# IOExpand.net
KiCad netlist of a schematic drawn in Altium Designer
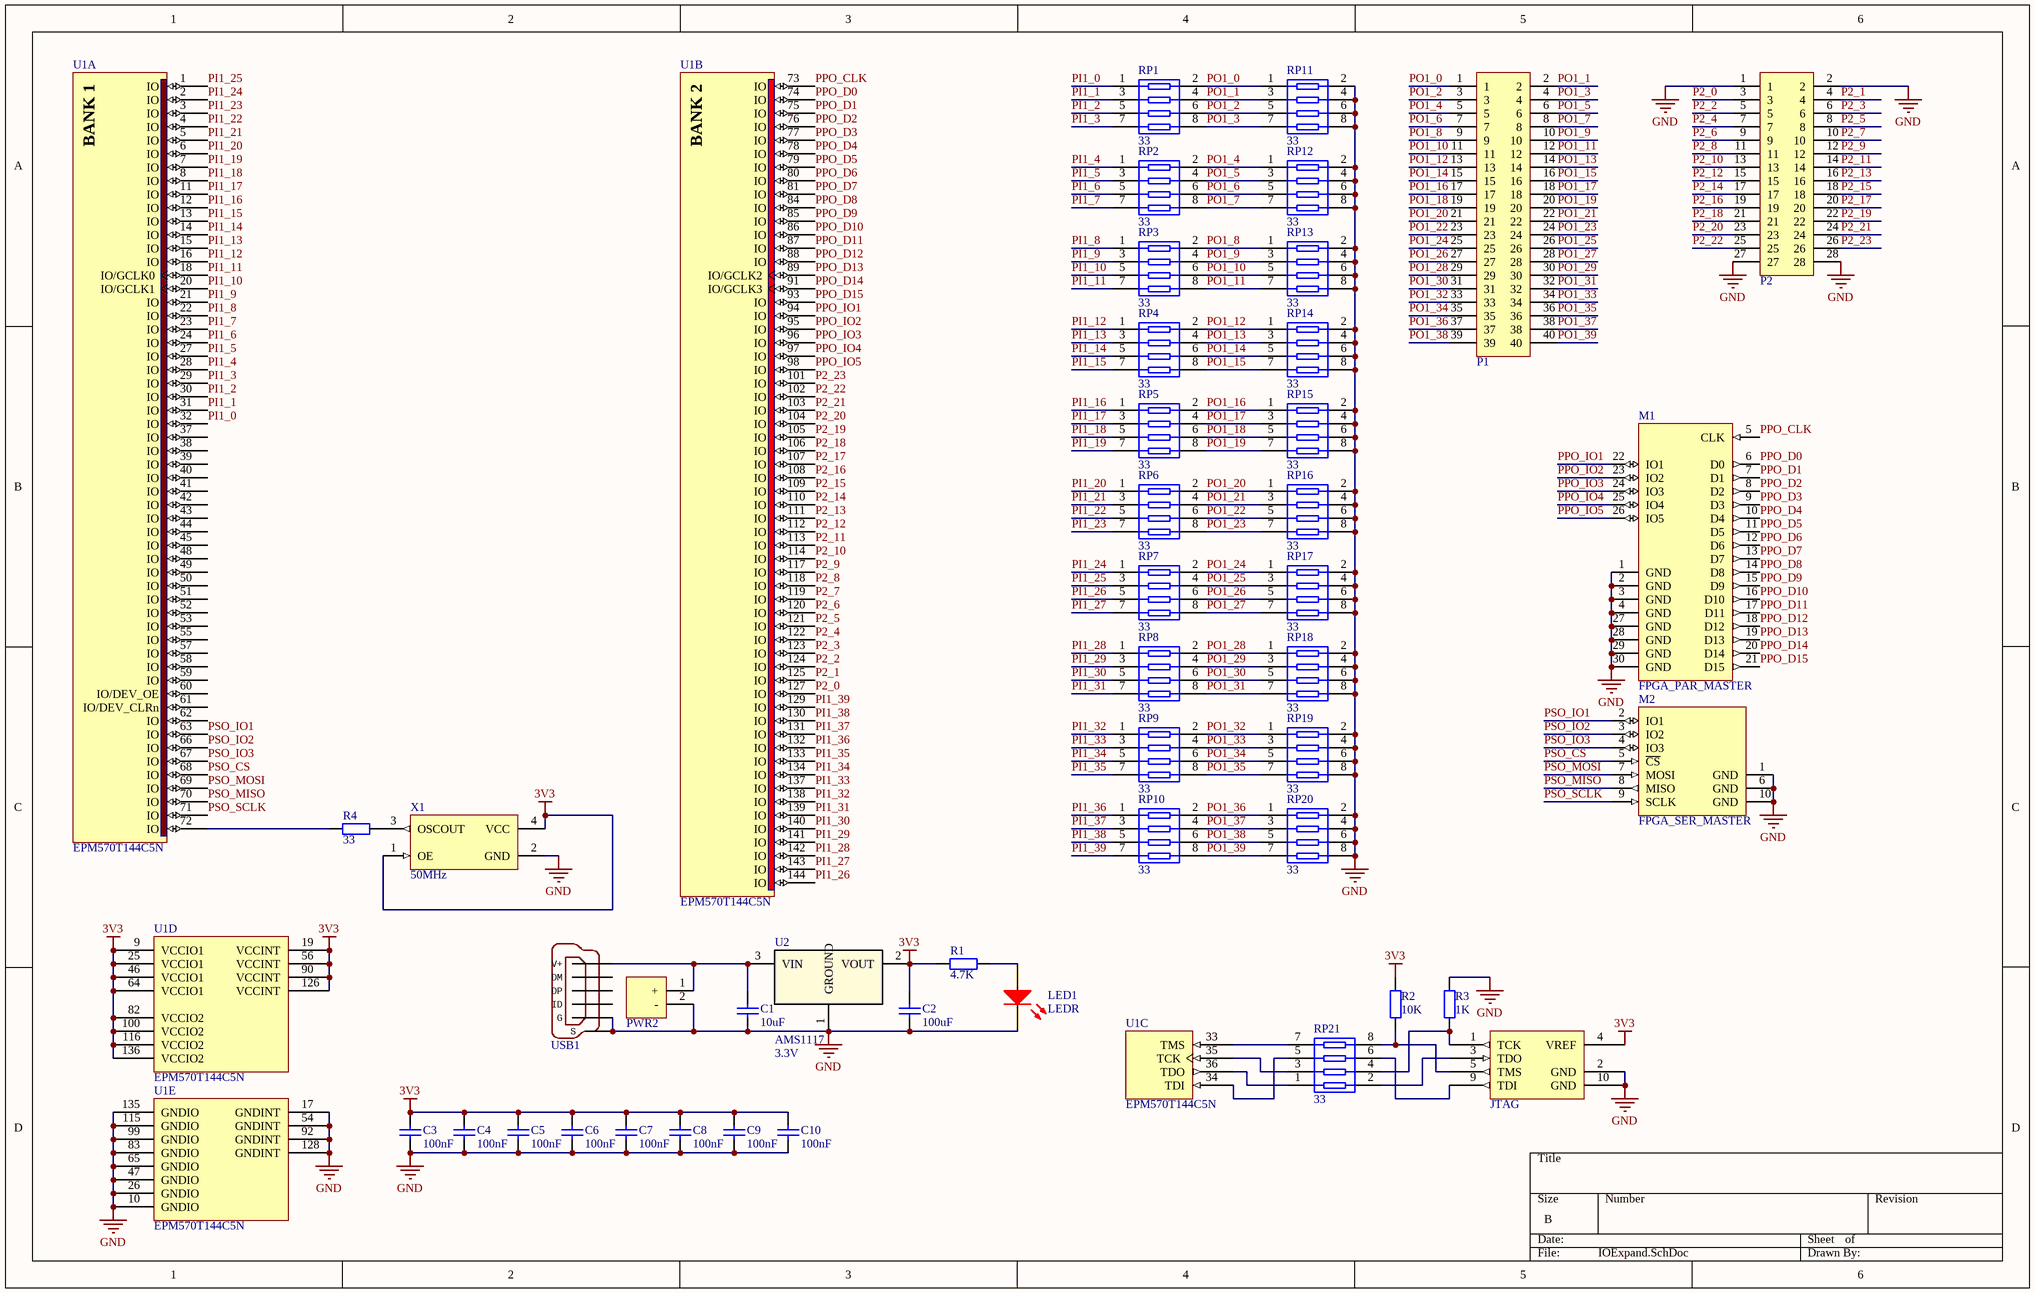
[diagram p0: IOExpand.SchDoc]

(export (version "E")
  (design (tool "Eeschema 10.0.6"))
  (components
    (comp (ref "C1")
      (value "10uF")
      (footprint "0805C")
      (description "MLCC")
      (libsource (lib "Misc") (part "MLCC"))
    )
    (comp (ref "C2")
      (value "100uF")
      (footprint "1206C")
      (description "MLCC")
      (libsource (lib "Misc") (part "MLCC"))
    )
    (comp (ref "C3")
      (value "100nF")
      (footprint "0603C")
      (description "MLCC")
      (libsource (lib "Misc") (part "MLCC"))
    )
    (comp (ref "C4")
      (value "100nF")
      (footprint "0603C")
      (description "MLCC")
      (libsource (lib "Misc") (part "MLCC"))
    )
    (comp (ref "C5")
      (value "100nF")
      (footprint "0603C")
      (description "MLCC")
      (libsource (lib "Misc") (part "MLCC"))
    )
    (comp (ref "C6")
      (value "100nF")
      (footprint "0603C")
      (description "MLCC")
      (libsource (lib "Misc") (part "MLCC"))
    )
    (comp (ref "C7")
      (value "100nF")
      (footprint "0603C")
      (description "MLCC")
      (libsource (lib "Misc") (part "MLCC"))
    )
    (comp (ref "C8")
      (value "100nF")
      (footprint "0603C")
      (description "MLCC")
      (libsource (lib "Misc") (part "MLCC"))
    )
    (comp (ref "C9")
      (value "100nF")
      (footprint "0603C")
      (description "MLCC")
      (libsource (lib "Misc") (part "MLCC"))
    )
    (comp (ref "C10")
      (value "100nF")
      (footprint "0603C")
      (description "MLCC")
      (libsource (lib "Misc") (part "MLCC"))
    )
    (comp (ref "JTAG")
      (value "JTAG_ALTERA")
      (footprint "JTAG10")
      (description "ALTERA JTAG port")
      (libsource (lib "JTAG") (part "JTAG_ALTERA"))
    )
    (comp (ref "LED1")
      (value "LEDR")
      (footprint "LED1206R")
      (description "RED LED")
      (libsource (lib "Misc") (part "LEDR"))
    )
    (comp (ref "M1")
      (value "FPGA_PAR_MASTER")
      (footprint "IDC30")
      (description "FPGA parallel port")
      (libsource (lib "Modules") (part "FPGA_PAR_MASTER"))
    )
    (comp (ref "M2")
      (value "FPGA_SER_MASTER")
      (footprint "IDC10")
      (description "FPGA serial port")
      (libsource (lib "Modules") (part "FPGA_SER_MASTER"))
    )
    (comp (ref "P1")
      (value "Dual 20 pin port")
      (footprint "201S2X20")
      (libsource (lib "Ports2.54") (part "DPORT20"))
    )
    (comp (ref "P2")
      (value "Dual 14 pin port")
      (footprint "201S2X14")
      (libsource (lib "Ports2.54") (part "DPORT14"))
    )
    (comp (ref "PWR2")
      (value "WPORT2_PWR")
      (footprint "VH3.96-POWER-2P")
      (description "2 pin power port")
      (libsource (lib "Ports3.96") (part "WPORT2_PWR"))
    )
    (comp (ref "R1")
      (value "4.7K")
      (footprint "0603R")
      (description "Resistor")
      (libsource (lib "Misc") (part "Resistor"))
    )
    (comp (ref "R2")
      (value "10K")
      (footprint "0603R")
      (description "Resistor")
      (libsource (lib "") (part "Resistor_1"))
    )
    (comp (ref "R3")
      (value "1K")
      (footprint "0603R")
      (description "Resistor")
      (libsource (lib "") (part "Resistor_1"))
    )
    (comp (ref "R4")
      (value "33")
      (footprint "0603R")
      (description "Resistor")
      (libsource (lib "Misc") (part "Resistor"))
    )
    (comp (ref "RP1")
      (value "33")
      (footprint "8P4R_0603")
      (description "Isolated Resistor Network")
      (fields (field (name "Comment") "Res Pack"))
      (libsource (lib "Misc") (part "Res Pack"))
    )
    (comp (ref "RP2")
      (value "33")
      (footprint "8P4R_0603")
      (description "Isolated Resistor Network")
      (fields (field (name "Comment") "Res Pack"))
      (libsource (lib "Misc") (part "Res Pack"))
    )
    (comp (ref "RP3")
      (value "33")
      (footprint "8P4R_0603")
      (description "Isolated Resistor Network")
      (fields (field (name "Comment") "Res Pack"))
      (libsource (lib "Misc") (part "Res Pack"))
    )
    (comp (ref "RP4")
      (value "33")
      (footprint "8P4R_0603")
      (description "Isolated Resistor Network")
      (fields (field (name "Comment") "Res Pack"))
      (libsource (lib "Misc") (part "Res Pack"))
    )
    (comp (ref "RP5")
      (value "33")
      (footprint "8P4R_0603")
      (description "Isolated Resistor Network")
      (fields (field (name "Comment") "Res Pack"))
      (libsource (lib "Misc") (part "Res Pack"))
    )
    (comp (ref "RP6")
      (value "33")
      (footprint "8P4R_0603")
      (description "Isolated Resistor Network")
      (fields (field (name "Comment") "Res Pack"))
      (libsource (lib "Misc") (part "Res Pack"))
    )
    (comp (ref "RP7")
      (value "33")
      (footprint "8P4R_0603")
      (description "Isolated Resistor Network")
      (fields (field (name "Comment") "Res Pack"))
      (libsource (lib "Misc") (part "Res Pack"))
    )
    (comp (ref "RP8")
      (value "33")
      (footprint "8P4R_0603")
      (description "Isolated Resistor Network")
      (fields (field (name "Comment") "Res Pack"))
      (libsource (lib "Misc") (part "Res Pack"))
    )
    (comp (ref "RP9")
      (value "33")
      (footprint "8P4R_0603")
      (description "Isolated Resistor Network")
      (fields (field (name "Comment") "Res Pack"))
      (libsource (lib "Misc") (part "Res Pack"))
    )
    (comp (ref "RP10")
      (value "33")
      (footprint "8P4R_0603")
      (description "Isolated Resistor Network")
      (fields (field (name "Comment") "Res Pack"))
      (libsource (lib "Misc") (part "Res Pack"))
    )
    (comp (ref "RP11")
      (value "33")
      (footprint "8P4R_0603")
      (description "Isolated Resistor Network")
      (fields (field (name "Comment") "Res Pack"))
      (libsource (lib "Misc") (part "Res Pack"))
    )
    (comp (ref "RP12")
      (value "33")
      (footprint "8P4R_0603")
      (description "Isolated Resistor Network")
      (fields (field (name "Comment") "Res Pack"))
      (libsource (lib "Misc") (part "Res Pack"))
    )
    (comp (ref "RP13")
      (value "33")
      (footprint "8P4R_0603")
      (description "Isolated Resistor Network")
      (fields (field (name "Comment") "Res Pack"))
      (libsource (lib "Misc") (part "Res Pack"))
    )
    (comp (ref "RP14")
      (value "33")
      (footprint "8P4R_0603")
      (description "Isolated Resistor Network")
      (fields (field (name "Comment") "Res Pack"))
      (libsource (lib "Misc") (part "Res Pack"))
    )
    (comp (ref "RP15")
      (value "33")
      (footprint "8P4R_0603")
      (description "Isolated Resistor Network")
      (fields (field (name "Comment") "Res Pack"))
      (libsource (lib "Misc") (part "Res Pack"))
    )
    (comp (ref "RP16")
      (value "33")
      (footprint "8P4R_0603")
      (description "Isolated Resistor Network")
      (fields (field (name "Comment") "Res Pack"))
      (libsource (lib "Misc") (part "Res Pack"))
    )
    (comp (ref "RP17")
      (value "33")
      (footprint "8P4R_0603")
      (description "Isolated Resistor Network")
      (fields (field (name "Comment") "Res Pack"))
      (libsource (lib "Misc") (part "Res Pack"))
    )
    (comp (ref "RP18")
      (value "33")
      (footprint "8P4R_0603")
      (description "Isolated Resistor Network")
      (fields (field (name "Comment") "Res Pack"))
      (libsource (lib "Misc") (part "Res Pack"))
    )
    (comp (ref "RP19")
      (value "33")
      (footprint "8P4R_0603")
      (description "Isolated Resistor Network")
      (fields (field (name "Comment") "Res Pack"))
      (libsource (lib "Misc") (part "Res Pack"))
    )
    (comp (ref "RP20")
      (value "33")
      (footprint "8P4R_0603")
      (description "Isolated Resistor Network")
      (fields (field (name "Comment") "Res Pack"))
      (libsource (lib "Misc") (part "Res Pack"))
    )
    (comp (ref "RP21")
      (value "33")
      (footprint "8P4R_0603")
      (description "Isolated Resistor Network")
      (fields (field (name "Comment") "Res Pack"))
      (libsource (lib "Misc") (part "Res Pack"))
    )
    (comp (ref "U1")
      (value "EPM570T144C5N")
      (footprint "TQFP144_N")
      (libsource (lib "Altera MAX II") (part "EPM570T144C5N"))
    )
    (comp (ref "U2")
      (value "AMS1117")
      (footprint "DCY4")
      (description "800mA LOW DROPOUT VOLTAGE REGULATOR")
      (fields (field (name "ALTIUM_VALUE") "3.3V"))
      (libsource (lib "LDO") (part "AMS1117"))
    )
    (comp (ref "USB1")
      (value "MICRO-USB")
      (footprint "USB-MICRO")
      (description "MICRO USB Connector")
      (libsource (lib "Misc") (part "MICRO-USB"))
    )
    (comp (ref "X1")
      (value "50MHz")
      (footprint "XTAL-3225")
      (description "Oscillator")
      (libsource (lib "XTAL") (part "Oscillator"))
    )
  )
  (nets
    (net (code "1") (name "/P2_0") (class "Default")
      (node (ref "P2") (pin "3") (pinfunction "3_3") (pintype "passive"))
      (node (ref "U1") (pin "127") (pinfunction "IO_127") (pintype "bidirectional"))
    )
    (net (code "2") (name "/P2_1") (class "Default")
      (node (ref "P2") (pin "4") (pinfunction "4_4") (pintype "passive"))
      (node (ref "U1") (pin "125") (pinfunction "IO_125") (pintype "bidirectional"))
    )
    (net (code "3") (name "/P2_2") (class "Default")
      (node (ref "P2") (pin "5") (pinfunction "5_5") (pintype "passive"))
      (node (ref "U1") (pin "124") (pinfunction "IO_124") (pintype "bidirectional"))
    )
    (net (code "4") (name "/P2_3") (class "Default")
      (node (ref "P2") (pin "6") (pinfunction "6_6") (pintype "passive"))
      (node (ref "U1") (pin "123") (pinfunction "IO_123") (pintype "bidirectional"))
    )
    (net (code "5") (name "/P2_4") (class "Default")
      (node (ref "P2") (pin "7") (pinfunction "7_7") (pintype "passive"))
      (node (ref "U1") (pin "122") (pinfunction "IO_122") (pintype "bidirectional"))
    )
    (net (code "6") (name "/P2_5") (class "Default")
      (node (ref "P2") (pin "8") (pinfunction "8_8") (pintype "passive"))
      (node (ref "U1") (pin "121") (pinfunction "IO_121") (pintype "bidirectional"))
    )
    (net (code "7") (name "/P2_6") (class "Default")
      (node (ref "P2") (pin "9") (pinfunction "9_9") (pintype "passive"))
      (node (ref "U1") (pin "120") (pinfunction "IO_120") (pintype "bidirectional"))
    )
    (net (code "8") (name "/P2_7") (class "Default")
      (node (ref "P2") (pin "10") (pinfunction "10_10") (pintype "passive"))
      (node (ref "U1") (pin "119") (pinfunction "IO_119") (pintype "bidirectional"))
    )
    (net (code "9") (name "/P2_8") (class "Default")
      (node (ref "P2") (pin "11") (pinfunction "11_11") (pintype "passive"))
      (node (ref "U1") (pin "118") (pinfunction "IO_118") (pintype "bidirectional"))
    )
    (net (code "10") (name "/P2_9") (class "Default")
      (node (ref "P2") (pin "12") (pinfunction "12_12") (pintype "passive"))
      (node (ref "U1") (pin "117") (pinfunction "IO_117") (pintype "bidirectional"))
    )
    (net (code "11") (name "/P2_10") (class "Default")
      (node (ref "P2") (pin "13") (pinfunction "13_13") (pintype "passive"))
      (node (ref "U1") (pin "114") (pinfunction "IO_114") (pintype "bidirectional"))
    )
    (net (code "12") (name "/P2_11") (class "Default")
      (node (ref "P2") (pin "14") (pinfunction "14_14") (pintype "passive"))
      (node (ref "U1") (pin "113") (pinfunction "IO_113") (pintype "bidirectional"))
    )
    (net (code "13") (name "/P2_12") (class "Default")
      (node (ref "P2") (pin "15") (pinfunction "15_15") (pintype "passive"))
      (node (ref "U1") (pin "112") (pinfunction "IO_112") (pintype "bidirectional"))
    )
    (net (code "14") (name "/P2_13") (class "Default")
      (node (ref "P2") (pin "16") (pinfunction "16_16") (pintype "passive"))
      (node (ref "U1") (pin "111") (pinfunction "IO_111") (pintype "bidirectional"))
    )
    (net (code "15") (name "/P2_14") (class "Default")
      (node (ref "P2") (pin "17") (pinfunction "17_17") (pintype "passive"))
      (node (ref "U1") (pin "110") (pinfunction "IO_110") (pintype "bidirectional"))
    )
    (net (code "16") (name "/P2_15") (class "Default")
      (node (ref "P2") (pin "18") (pinfunction "18_18") (pintype "passive"))
      (node (ref "U1") (pin "109") (pinfunction "IO_109") (pintype "bidirectional"))
    )
    (net (code "17") (name "/P2_16") (class "Default")
      (node (ref "P2") (pin "19") (pinfunction "19_19") (pintype "passive"))
      (node (ref "U1") (pin "108") (pinfunction "IO_108") (pintype "bidirectional"))
    )
    (net (code "18") (name "/P2_17") (class "Default")
      (node (ref "P2") (pin "20") (pinfunction "20_20") (pintype "passive"))
      (node (ref "U1") (pin "107") (pinfunction "IO_107") (pintype "bidirectional"))
    )
    (net (code "19") (name "/P2_18") (class "Default")
      (node (ref "P2") (pin "21") (pinfunction "21_21") (pintype "passive"))
      (node (ref "U1") (pin "106") (pinfunction "IO_106") (pintype "bidirectional"))
    )
    (net (code "20") (name "/P2_19") (class "Default")
      (node (ref "P2") (pin "22") (pinfunction "22_22") (pintype "passive"))
      (node (ref "U1") (pin "105") (pinfunction "IO_105") (pintype "bidirectional"))
    )
    (net (code "21") (name "/P2_20") (class "Default")
      (node (ref "P2") (pin "23") (pinfunction "23_23") (pintype "passive"))
      (node (ref "U1") (pin "104") (pinfunction "IO_104") (pintype "bidirectional"))
    )
    (net (code "22") (name "/P2_21") (class "Default")
      (node (ref "P2") (pin "24") (pinfunction "24_24") (pintype "passive"))
      (node (ref "U1") (pin "103") (pinfunction "IO_103") (pintype "bidirectional"))
    )
    (net (code "23") (name "/P2_22") (class "Default")
      (node (ref "P2") (pin "25") (pinfunction "25_25") (pintype "passive"))
      (node (ref "U1") (pin "102") (pinfunction "IO_102") (pintype "bidirectional"))
    )
    (net (code "24") (name "/P2_23") (class "Default")
      (node (ref "P2") (pin "26") (pinfunction "26_26") (pintype "passive"))
      (node (ref "U1") (pin "101") (pinfunction "IO_101") (pintype "bidirectional"))
    )
    (net (code "25") (name "/PI1_0") (class "Default")
      (node (ref "RP1") (pin "1") (pinfunction "1_1") (pintype "passive"))
      (node (ref "U1") (pin "32") (pinfunction "IO_32") (pintype "bidirectional"))
    )
    (net (code "26") (name "/PI1_1") (class "Default")
      (node (ref "RP1") (pin "3") (pinfunction "3_3") (pintype "passive"))
      (node (ref "U1") (pin "31") (pinfunction "IO_31") (pintype "bidirectional"))
    )
    (net (code "27") (name "/PI1_2") (class "Default")
      (node (ref "RP1") (pin "5") (pinfunction "5_5") (pintype "passive"))
      (node (ref "U1") (pin "30") (pinfunction "IO_30") (pintype "bidirectional"))
    )
    (net (code "28") (name "/PI1_3") (class "Default")
      (node (ref "RP1") (pin "7") (pinfunction "7_7") (pintype "passive"))
      (node (ref "U1") (pin "29") (pinfunction "IO_29") (pintype "bidirectional"))
    )
    (net (code "29") (name "/PI1_4") (class "Default")
      (node (ref "RP2") (pin "1") (pinfunction "1_1") (pintype "passive"))
      (node (ref "U1") (pin "28") (pinfunction "IO_28") (pintype "bidirectional"))
    )
    (net (code "30") (name "/PI1_5") (class "Default")
      (node (ref "RP2") (pin "3") (pinfunction "3_3") (pintype "passive"))
      (node (ref "U1") (pin "27") (pinfunction "IO_27") (pintype "bidirectional"))
    )
    (net (code "31") (name "/PI1_6") (class "Default")
      (node (ref "RP2") (pin "5") (pinfunction "5_5") (pintype "passive"))
      (node (ref "U1") (pin "24") (pinfunction "IO_24") (pintype "bidirectional"))
    )
    (net (code "32") (name "/PI1_7") (class "Default")
      (node (ref "RP2") (pin "7") (pinfunction "7_7") (pintype "passive"))
      (node (ref "U1") (pin "23") (pinfunction "IO_23") (pintype "bidirectional"))
    )
    (net (code "33") (name "/PI1_8") (class "Default")
      (node (ref "RP3") (pin "1") (pinfunction "1_1") (pintype "passive"))
      (node (ref "U1") (pin "22") (pinfunction "IO_22") (pintype "bidirectional"))
    )
    (net (code "34") (name "/PI1_9") (class "Default")
      (node (ref "RP3") (pin "3") (pinfunction "3_3") (pintype "passive"))
      (node (ref "U1") (pin "21") (pinfunction "IO_21") (pintype "bidirectional"))
    )
    (net (code "35") (name "/PI1_10") (class "Default")
      (node (ref "RP3") (pin "5") (pinfunction "5_5") (pintype "passive"))
      (node (ref "U1") (pin "20") (pinfunction "IO/GCLK1_20") (pintype "bidirectional"))
    )
    (net (code "36") (name "/PI1_11") (class "Default")
      (node (ref "RP3") (pin "7") (pinfunction "7_7") (pintype "passive"))
      (node (ref "U1") (pin "18") (pinfunction "IO/GCLK0_18") (pintype "bidirectional"))
    )
    (net (code "37") (name "/PI1_12") (class "Default")
      (node (ref "RP4") (pin "1") (pinfunction "1_1") (pintype "passive"))
      (node (ref "U1") (pin "16") (pinfunction "IO_16") (pintype "bidirectional"))
    )
    (net (code "38") (name "/PI1_13") (class "Default")
      (node (ref "RP4") (pin "3") (pinfunction "3_3") (pintype "passive"))
      (node (ref "U1") (pin "15") (pinfunction "IO_15") (pintype "bidirectional"))
    )
    (net (code "39") (name "/PI1_14") (class "Default")
      (node (ref "RP4") (pin "5") (pinfunction "5_5") (pintype "passive"))
      (node (ref "U1") (pin "14") (pinfunction "IO_14") (pintype "bidirectional"))
    )
    (net (code "40") (name "/PI1_15") (class "Default")
      (node (ref "RP4") (pin "7") (pinfunction "7_7") (pintype "passive"))
      (node (ref "U1") (pin "13") (pinfunction "IO_13") (pintype "bidirectional"))
    )
    (net (code "41") (name "/PI1_16") (class "Default")
      (node (ref "RP5") (pin "1") (pinfunction "1_1") (pintype "passive"))
      (node (ref "U1") (pin "12") (pinfunction "IO_12") (pintype "bidirectional"))
    )
    (net (code "42") (name "/PI1_17") (class "Default")
      (node (ref "RP5") (pin "3") (pinfunction "3_3") (pintype "passive"))
      (node (ref "U1") (pin "11") (pinfunction "IO_11") (pintype "bidirectional"))
    )
    (net (code "43") (name "/PI1_18") (class "Default")
      (node (ref "RP5") (pin "5") (pinfunction "5_5") (pintype "passive"))
      (node (ref "U1") (pin "8") (pinfunction "IO_8") (pintype "bidirectional"))
    )
    (net (code "44") (name "/PI1_19") (class "Default")
      (node (ref "RP5") (pin "7") (pinfunction "7_7") (pintype "passive"))
      (node (ref "U1") (pin "7") (pinfunction "IO_7") (pintype "bidirectional"))
    )
    (net (code "45") (name "/PI1_20") (class "Default")
      (node (ref "RP6") (pin "1") (pinfunction "1_1") (pintype "passive"))
      (node (ref "U1") (pin "6") (pinfunction "IO_6") (pintype "bidirectional"))
    )
    (net (code "46") (name "/PI1_21") (class "Default")
      (node (ref "RP6") (pin "3") (pinfunction "3_3") (pintype "passive"))
      (node (ref "U1") (pin "5") (pinfunction "IO_5") (pintype "bidirectional"))
    )
    (net (code "47") (name "/PI1_22") (class "Default")
      (node (ref "RP6") (pin "5") (pinfunction "5_5") (pintype "passive"))
      (node (ref "U1") (pin "4") (pinfunction "IO_4") (pintype "bidirectional"))
    )
    (net (code "48") (name "/PI1_23") (class "Default")
      (node (ref "RP6") (pin "7") (pinfunction "7_7") (pintype "passive"))
      (node (ref "U1") (pin "3") (pinfunction "IO_3") (pintype "bidirectional"))
    )
    (net (code "49") (name "/PI1_24") (class "Default")
      (node (ref "RP7") (pin "1") (pinfunction "1_1") (pintype "passive"))
      (node (ref "U1") (pin "2") (pinfunction "IO_2") (pintype "bidirectional"))
    )
    (net (code "50") (name "/PI1_25") (class "Default")
      (node (ref "RP7") (pin "3") (pinfunction "3_3") (pintype "passive"))
      (node (ref "U1") (pin "1") (pinfunction "IO_1") (pintype "bidirectional"))
    )
    (net (code "51") (name "/PI1_26") (class "Default")
      (node (ref "RP7") (pin "5") (pinfunction "5_5") (pintype "passive"))
      (node (ref "U1") (pin "144") (pinfunction "IO_144") (pintype "bidirectional"))
    )
    (net (code "52") (name "/PI1_27") (class "Default")
      (node (ref "RP7") (pin "7") (pinfunction "7_7") (pintype "passive"))
      (node (ref "U1") (pin "143") (pinfunction "IO_143") (pintype "bidirectional"))
    )
    (net (code "53") (name "/PI1_28") (class "Default")
      (node (ref "RP8") (pin "1") (pinfunction "1_1") (pintype "passive"))
      (node (ref "U1") (pin "142") (pinfunction "IO_142") (pintype "bidirectional"))
    )
    (net (code "54") (name "/PI1_29") (class "Default")
      (node (ref "RP8") (pin "3") (pinfunction "3_3") (pintype "passive"))
      (node (ref "U1") (pin "141") (pinfunction "IO_141") (pintype "bidirectional"))
    )
    (net (code "55") (name "/PI1_30") (class "Default")
      (node (ref "RP8") (pin "5") (pinfunction "5_5") (pintype "passive"))
      (node (ref "U1") (pin "140") (pinfunction "IO_140") (pintype "bidirectional"))
    )
    (net (code "56") (name "/PI1_31") (class "Default")
      (node (ref "RP8") (pin "7") (pinfunction "7_7") (pintype "passive"))
      (node (ref "U1") (pin "139") (pinfunction "IO_139") (pintype "bidirectional"))
    )
    (net (code "57") (name "/PI1_32") (class "Default")
      (node (ref "RP9") (pin "1") (pinfunction "1_1") (pintype "passive"))
      (node (ref "U1") (pin "138") (pinfunction "IO_138") (pintype "bidirectional"))
    )
    (net (code "58") (name "/PI1_33") (class "Default")
      (node (ref "RP9") (pin "3") (pinfunction "3_3") (pintype "passive"))
      (node (ref "U1") (pin "137") (pinfunction "IO_137") (pintype "bidirectional"))
    )
    (net (code "59") (name "/PI1_34") (class "Default")
      (node (ref "RP9") (pin "5") (pinfunction "5_5") (pintype "passive"))
      (node (ref "U1") (pin "134") (pinfunction "IO_134") (pintype "bidirectional"))
    )
    (net (code "60") (name "/PI1_35") (class "Default")
      (node (ref "RP9") (pin "7") (pinfunction "7_7") (pintype "passive"))
      (node (ref "U1") (pin "133") (pinfunction "IO_133") (pintype "bidirectional"))
    )
    (net (code "61") (name "/PI1_36") (class "Default")
      (node (ref "RP10") (pin "1") (pinfunction "1_1") (pintype "passive"))
      (node (ref "U1") (pin "132") (pinfunction "IO_132") (pintype "bidirectional"))
    )
    (net (code "62") (name "/PI1_37") (class "Default")
      (node (ref "RP10") (pin "3") (pinfunction "3_3") (pintype "passive"))
      (node (ref "U1") (pin "131") (pinfunction "IO_131") (pintype "bidirectional"))
    )
    (net (code "63") (name "/PI1_38") (class "Default")
      (node (ref "RP10") (pin "5") (pinfunction "5_5") (pintype "passive"))
      (node (ref "U1") (pin "130") (pinfunction "IO_130") (pintype "bidirectional"))
    )
    (net (code "64") (name "/PI1_39") (class "Default")
      (node (ref "RP10") (pin "7") (pinfunction "7_7") (pintype "passive"))
      (node (ref "U1") (pin "129") (pinfunction "IO_129") (pintype "bidirectional"))
    )
    (net (code "65") (name "/PO1_0") (class "Default")
      (node (ref "P1") (pin "1") (pinfunction "1_1") (pintype "passive"))
      (node (ref "RP1") (pin "2") (pinfunction "2_2") (pintype "passive"))
      (node (ref "RP11") (pin "1") (pinfunction "1_1") (pintype "passive"))
    )
    (net (code "66") (name "/PO1_1") (class "Default")
      (node (ref "P1") (pin "2") (pinfunction "2_2") (pintype "passive"))
      (node (ref "RP1") (pin "4") (pinfunction "4_4") (pintype "passive"))
      (node (ref "RP11") (pin "3") (pinfunction "3_3") (pintype "passive"))
    )
    (net (code "67") (name "/PO1_2") (class "Default")
      (node (ref "P1") (pin "3") (pinfunction "3_3") (pintype "passive"))
      (node (ref "RP1") (pin "6") (pinfunction "6_6") (pintype "passive"))
      (node (ref "RP11") (pin "5") (pinfunction "5_5") (pintype "passive"))
    )
    (net (code "68") (name "/PO1_3") (class "Default")
      (node (ref "P1") (pin "4") (pinfunction "4_4") (pintype "passive"))
      (node (ref "RP1") (pin "8") (pinfunction "8_8") (pintype "passive"))
      (node (ref "RP11") (pin "7") (pinfunction "7_7") (pintype "passive"))
    )
    (net (code "69") (name "/PO1_4") (class "Default")
      (node (ref "P1") (pin "5") (pinfunction "5_5") (pintype "passive"))
      (node (ref "RP12") (pin "1") (pinfunction "1_1") (pintype "passive"))
      (node (ref "RP2") (pin "2") (pinfunction "2_2") (pintype "passive"))
    )
    (net (code "70") (name "/PO1_5") (class "Default")
      (node (ref "P1") (pin "6") (pinfunction "6_6") (pintype "passive"))
      (node (ref "RP12") (pin "3") (pinfunction "3_3") (pintype "passive"))
      (node (ref "RP2") (pin "4") (pinfunction "4_4") (pintype "passive"))
    )
    (net (code "71") (name "/PO1_6") (class "Default")
      (node (ref "P1") (pin "7") (pinfunction "7_7") (pintype "passive"))
      (node (ref "RP12") (pin "5") (pinfunction "5_5") (pintype "passive"))
      (node (ref "RP2") (pin "6") (pinfunction "6_6") (pintype "passive"))
    )
    (net (code "72") (name "/PO1_7") (class "Default")
      (node (ref "P1") (pin "8") (pinfunction "8_8") (pintype "passive"))
      (node (ref "RP12") (pin "7") (pinfunction "7_7") (pintype "passive"))
      (node (ref "RP2") (pin "8") (pinfunction "8_8") (pintype "passive"))
    )
    (net (code "73") (name "/PO1_8") (class "Default")
      (node (ref "P1") (pin "9") (pinfunction "9_9") (pintype "passive"))
      (node (ref "RP13") (pin "1") (pinfunction "1_1") (pintype "passive"))
      (node (ref "RP3") (pin "2") (pinfunction "2_2") (pintype "passive"))
    )
    (net (code "74") (name "/PO1_9") (class "Default")
      (node (ref "P1") (pin "10") (pinfunction "10_10") (pintype "passive"))
      (node (ref "RP13") (pin "3") (pinfunction "3_3") (pintype "passive"))
      (node (ref "RP3") (pin "4") (pinfunction "4_4") (pintype "passive"))
    )
    (net (code "75") (name "/PO1_10") (class "Default")
      (node (ref "P1") (pin "11") (pinfunction "11_11") (pintype "passive"))
      (node (ref "RP13") (pin "5") (pinfunction "5_5") (pintype "passive"))
      (node (ref "RP3") (pin "6") (pinfunction "6_6") (pintype "passive"))
    )
    (net (code "76") (name "/PO1_11") (class "Default")
      (node (ref "P1") (pin "12") (pinfunction "12_12") (pintype "passive"))
      (node (ref "RP13") (pin "7") (pinfunction "7_7") (pintype "passive"))
      (node (ref "RP3") (pin "8") (pinfunction "8_8") (pintype "passive"))
    )
    (net (code "77") (name "/PO1_12") (class "Default")
      (node (ref "P1") (pin "13") (pinfunction "13_13") (pintype "passive"))
      (node (ref "RP14") (pin "1") (pinfunction "1_1") (pintype "passive"))
      (node (ref "RP4") (pin "2") (pinfunction "2_2") (pintype "passive"))
    )
    (net (code "78") (name "/PO1_13") (class "Default")
      (node (ref "P1") (pin "14") (pinfunction "14_14") (pintype "passive"))
      (node (ref "RP14") (pin "3") (pinfunction "3_3") (pintype "passive"))
      (node (ref "RP4") (pin "4") (pinfunction "4_4") (pintype "passive"))
    )
    (net (code "79") (name "/PO1_14") (class "Default")
      (node (ref "P1") (pin "15") (pinfunction "15_15") (pintype "passive"))
      (node (ref "RP14") (pin "5") (pinfunction "5_5") (pintype "passive"))
      (node (ref "RP4") (pin "6") (pinfunction "6_6") (pintype "passive"))
    )
    (net (code "80") (name "/PO1_15") (class "Default")
      (node (ref "P1") (pin "16") (pinfunction "16_16") (pintype "passive"))
      (node (ref "RP14") (pin "7") (pinfunction "7_7") (pintype "passive"))
      (node (ref "RP4") (pin "8") (pinfunction "8_8") (pintype "passive"))
    )
    (net (code "81") (name "/PO1_16") (class "Default")
      (node (ref "P1") (pin "17") (pinfunction "17_17") (pintype "passive"))
      (node (ref "RP15") (pin "1") (pinfunction "1_1") (pintype "passive"))
      (node (ref "RP5") (pin "2") (pinfunction "2_2") (pintype "passive"))
    )
    (net (code "82") (name "/PO1_17") (class "Default")
      (node (ref "P1") (pin "18") (pinfunction "18_18") (pintype "passive"))
      (node (ref "RP15") (pin "3") (pinfunction "3_3") (pintype "passive"))
      (node (ref "RP5") (pin "4") (pinfunction "4_4") (pintype "passive"))
    )
    (net (code "83") (name "/PO1_18") (class "Default")
      (node (ref "P1") (pin "19") (pinfunction "19_19") (pintype "passive"))
      (node (ref "RP15") (pin "5") (pinfunction "5_5") (pintype "passive"))
      (node (ref "RP5") (pin "6") (pinfunction "6_6") (pintype "passive"))
    )
    (net (code "84") (name "/PO1_19") (class "Default")
      (node (ref "P1") (pin "20") (pinfunction "20_20") (pintype "passive"))
      (node (ref "RP15") (pin "7") (pinfunction "7_7") (pintype "passive"))
      (node (ref "RP5") (pin "8") (pinfunction "8_8") (pintype "passive"))
    )
    (net (code "85") (name "/PO1_20") (class "Default")
      (node (ref "P1") (pin "21") (pinfunction "21_21") (pintype "passive"))
      (node (ref "RP16") (pin "1") (pinfunction "1_1") (pintype "passive"))
      (node (ref "RP6") (pin "2") (pinfunction "2_2") (pintype "passive"))
    )
    (net (code "86") (name "/PO1_21") (class "Default")
      (node (ref "P1") (pin "22") (pinfunction "22_22") (pintype "passive"))
      (node (ref "RP16") (pin "3") (pinfunction "3_3") (pintype "passive"))
      (node (ref "RP6") (pin "4") (pinfunction "4_4") (pintype "passive"))
    )
    (net (code "87") (name "/PO1_22") (class "Default")
      (node (ref "P1") (pin "23") (pinfunction "23_23") (pintype "passive"))
      (node (ref "RP16") (pin "5") (pinfunction "5_5") (pintype "passive"))
      (node (ref "RP6") (pin "6") (pinfunction "6_6") (pintype "passive"))
    )
    (net (code "88") (name "/PO1_23") (class "Default")
      (node (ref "P1") (pin "24") (pinfunction "24_24") (pintype "passive"))
      (node (ref "RP16") (pin "7") (pinfunction "7_7") (pintype "passive"))
      (node (ref "RP6") (pin "8") (pinfunction "8_8") (pintype "passive"))
    )
    (net (code "89") (name "/PO1_24") (class "Default")
      (node (ref "P1") (pin "25") (pinfunction "25_25") (pintype "passive"))
      (node (ref "RP17") (pin "1") (pinfunction "1_1") (pintype "passive"))
      (node (ref "RP7") (pin "2") (pinfunction "2_2") (pintype "passive"))
    )
    (net (code "90") (name "/PO1_25") (class "Default")
      (node (ref "P1") (pin "26") (pinfunction "26_26") (pintype "passive"))
      (node (ref "RP17") (pin "3") (pinfunction "3_3") (pintype "passive"))
      (node (ref "RP7") (pin "4") (pinfunction "4_4") (pintype "passive"))
    )
    (net (code "91") (name "/PO1_26") (class "Default")
      (node (ref "P1") (pin "27") (pinfunction "27_27") (pintype "passive"))
      (node (ref "RP17") (pin "5") (pinfunction "5_5") (pintype "passive"))
      (node (ref "RP7") (pin "6") (pinfunction "6_6") (pintype "passive"))
    )
    (net (code "92") (name "/PO1_27") (class "Default")
      (node (ref "P1") (pin "28") (pinfunction "28_28") (pintype "passive"))
      (node (ref "RP17") (pin "7") (pinfunction "7_7") (pintype "passive"))
      (node (ref "RP7") (pin "8") (pinfunction "8_8") (pintype "passive"))
    )
    (net (code "93") (name "/PO1_28") (class "Default")
      (node (ref "P1") (pin "29") (pinfunction "29_29") (pintype "passive"))
      (node (ref "RP18") (pin "1") (pinfunction "1_1") (pintype "passive"))
      (node (ref "RP8") (pin "2") (pinfunction "2_2") (pintype "passive"))
    )
    (net (code "94") (name "/PO1_29") (class "Default")
      (node (ref "P1") (pin "30") (pinfunction "30_30") (pintype "passive"))
      (node (ref "RP18") (pin "3") (pinfunction "3_3") (pintype "passive"))
      (node (ref "RP8") (pin "4") (pinfunction "4_4") (pintype "passive"))
    )
    (net (code "95") (name "/PO1_30") (class "Default")
      (node (ref "P1") (pin "31") (pinfunction "31_31") (pintype "passive"))
      (node (ref "RP18") (pin "5") (pinfunction "5_5") (pintype "passive"))
      (node (ref "RP8") (pin "6") (pinfunction "6_6") (pintype "passive"))
    )
    (net (code "96") (name "/PO1_31") (class "Default")
      (node (ref "P1") (pin "32") (pinfunction "32_32") (pintype "passive"))
      (node (ref "RP18") (pin "7") (pinfunction "7_7") (pintype "passive"))
      (node (ref "RP8") (pin "8") (pinfunction "8_8") (pintype "passive"))
    )
    (net (code "97") (name "/PO1_32") (class "Default")
      (node (ref "P1") (pin "33") (pinfunction "33_33") (pintype "passive"))
      (node (ref "RP19") (pin "1") (pinfunction "1_1") (pintype "passive"))
      (node (ref "RP9") (pin "2") (pinfunction "2_2") (pintype "passive"))
    )
    (net (code "98") (name "/PO1_33") (class "Default")
      (node (ref "P1") (pin "34") (pinfunction "34_34") (pintype "passive"))
      (node (ref "RP19") (pin "3") (pinfunction "3_3") (pintype "passive"))
      (node (ref "RP9") (pin "4") (pinfunction "4_4") (pintype "passive"))
    )
    (net (code "99") (name "/PO1_34") (class "Default")
      (node (ref "P1") (pin "35") (pinfunction "35_35") (pintype "passive"))
      (node (ref "RP19") (pin "5") (pinfunction "5_5") (pintype "passive"))
      (node (ref "RP9") (pin "6") (pinfunction "6_6") (pintype "passive"))
    )
    (net (code "100") (name "/PO1_35") (class "Default")
      (node (ref "P1") (pin "36") (pinfunction "36_36") (pintype "passive"))
      (node (ref "RP19") (pin "7") (pinfunction "7_7") (pintype "passive"))
      (node (ref "RP9") (pin "8") (pinfunction "8_8") (pintype "passive"))
    )
    (net (code "101") (name "/PO1_36") (class "Default")
      (node (ref "P1") (pin "37") (pinfunction "37_37") (pintype "passive"))
      (node (ref "RP10") (pin "2") (pinfunction "2_2") (pintype "passive"))
      (node (ref "RP20") (pin "1") (pinfunction "1_1") (pintype "passive"))
    )
    (net (code "102") (name "/PO1_37") (class "Default")
      (node (ref "P1") (pin "38") (pinfunction "38_38") (pintype "passive"))
      (node (ref "RP10") (pin "4") (pinfunction "4_4") (pintype "passive"))
      (node (ref "RP20") (pin "3") (pinfunction "3_3") (pintype "passive"))
    )
    (net (code "103") (name "/PO1_38") (class "Default")
      (node (ref "P1") (pin "39") (pinfunction "39_39") (pintype "passive"))
      (node (ref "RP10") (pin "6") (pinfunction "6_6") (pintype "passive"))
      (node (ref "RP20") (pin "5") (pinfunction "5_5") (pintype "passive"))
    )
    (net (code "104") (name "/PO1_39") (class "Default")
      (node (ref "P1") (pin "40") (pinfunction "40_40") (pintype "passive"))
      (node (ref "RP10") (pin "8") (pinfunction "8_8") (pintype "passive"))
      (node (ref "RP20") (pin "7") (pinfunction "7_7") (pintype "passive"))
    )
    (net (code "105") (name "/PPO_CLK") (class "Default")
      (node (ref "M1") (pin "5") (pinfunction "CLK_5") (pintype "input"))
      (node (ref "U1") (pin "73") (pinfunction "IO_73") (pintype "bidirectional"))
    )
    (net (code "106") (name "/PPO_D0") (class "Default")
      (node (ref "M1") (pin "6") (pinfunction "D0_6") (pintype "output"))
      (node (ref "U1") (pin "74") (pinfunction "IO_74") (pintype "bidirectional"))
    )
    (net (code "107") (name "/PPO_D1") (class "Default")
      (node (ref "M1") (pin "7") (pinfunction "D1_7") (pintype "output"))
      (node (ref "U1") (pin "75") (pinfunction "IO_75") (pintype "bidirectional"))
    )
    (net (code "108") (name "/PPO_D2") (class "Default")
      (node (ref "M1") (pin "8") (pinfunction "D2_8") (pintype "output"))
      (node (ref "U1") (pin "76") (pinfunction "IO_76") (pintype "bidirectional"))
    )
    (net (code "109") (name "/PPO_D3") (class "Default")
      (node (ref "M1") (pin "9") (pinfunction "D3_9") (pintype "output"))
      (node (ref "U1") (pin "77") (pinfunction "IO_77") (pintype "bidirectional"))
    )
    (net (code "110") (name "/PPO_D4") (class "Default")
      (node (ref "M1") (pin "10") (pinfunction "D4_10") (pintype "output"))
      (node (ref "U1") (pin "78") (pinfunction "IO_78") (pintype "bidirectional"))
    )
    (net (code "111") (name "/PPO_D5") (class "Default")
      (node (ref "M1") (pin "11") (pinfunction "D5_11") (pintype "output"))
      (node (ref "U1") (pin "79") (pinfunction "IO_79") (pintype "bidirectional"))
    )
    (net (code "112") (name "/PPO_D6") (class "Default")
      (node (ref "M1") (pin "12") (pinfunction "D6_12") (pintype "output"))
      (node (ref "U1") (pin "80") (pinfunction "IO_80") (pintype "bidirectional"))
    )
    (net (code "113") (name "/PPO_D7") (class "Default")
      (node (ref "M1") (pin "13") (pinfunction "D7_13") (pintype "output"))
      (node (ref "U1") (pin "81") (pinfunction "IO_81") (pintype "bidirectional"))
    )
    (net (code "114") (name "/PPO_D8") (class "Default")
      (node (ref "M1") (pin "14") (pinfunction "D8_14") (pintype "output"))
      (node (ref "U1") (pin "84") (pinfunction "IO_84") (pintype "bidirectional"))
    )
    (net (code "115") (name "/PPO_D9") (class "Default")
      (node (ref "M1") (pin "15") (pinfunction "D9_15") (pintype "output"))
      (node (ref "U1") (pin "85") (pinfunction "IO_85") (pintype "bidirectional"))
    )
    (net (code "116") (name "/PPO_D10") (class "Default")
      (node (ref "M1") (pin "16") (pinfunction "D10_16") (pintype "output"))
      (node (ref "U1") (pin "86") (pinfunction "IO_86") (pintype "bidirectional"))
    )
    (net (code "117") (name "/PPO_D11") (class "Default")
      (node (ref "M1") (pin "17") (pinfunction "D11_17") (pintype "output"))
      (node (ref "U1") (pin "87") (pinfunction "IO_87") (pintype "bidirectional"))
    )
    (net (code "118") (name "/PPO_D12") (class "Default")
      (node (ref "M1") (pin "18") (pinfunction "D12_18") (pintype "output"))
      (node (ref "U1") (pin "88") (pinfunction "IO_88") (pintype "bidirectional"))
    )
    (net (code "119") (name "/PPO_D13") (class "Default")
      (node (ref "M1") (pin "19") (pinfunction "D13_19") (pintype "output"))
      (node (ref "U1") (pin "89") (pinfunction "IO/GCLK2_89") (pintype "bidirectional"))
    )
    (net (code "120") (name "/PPO_D14") (class "Default")
      (node (ref "M1") (pin "20") (pinfunction "D14_20") (pintype "output"))
      (node (ref "U1") (pin "91") (pinfunction "IO/GCLK3_91") (pintype "bidirectional"))
    )
    (net (code "121") (name "/PPO_D15") (class "Default")
      (node (ref "M1") (pin "21") (pinfunction "D15_21") (pintype "output"))
      (node (ref "U1") (pin "93") (pinfunction "IO_93") (pintype "bidirectional"))
    )
    (net (code "122") (name "/PPO_IO1") (class "Default")
      (node (ref "M1") (pin "22") (pinfunction "IO1_22") (pintype "bidirectional"))
      (node (ref "U1") (pin "94") (pinfunction "IO_94") (pintype "bidirectional"))
    )
    (net (code "123") (name "/PPO_IO2") (class "Default")
      (node (ref "M1") (pin "23") (pinfunction "IO2_23") (pintype "bidirectional"))
      (node (ref "U1") (pin "95") (pinfunction "IO_95") (pintype "bidirectional"))
    )
    (net (code "124") (name "/PPO_IO3") (class "Default")
      (node (ref "M1") (pin "24") (pinfunction "IO3_24") (pintype "bidirectional"))
      (node (ref "U1") (pin "96") (pinfunction "IO_96") (pintype "bidirectional"))
    )
    (net (code "125") (name "/PPO_IO4") (class "Default")
      (node (ref "M1") (pin "25") (pinfunction "IO4_25") (pintype "bidirectional"))
      (node (ref "U1") (pin "97") (pinfunction "IO_97") (pintype "bidirectional"))
    )
    (net (code "126") (name "/PPO_IO5") (class "Default")
      (node (ref "M1") (pin "26") (pinfunction "IO5_26") (pintype "bidirectional"))
      (node (ref "U1") (pin "98") (pinfunction "IO_98") (pintype "bidirectional"))
    )
    (net (code "127") (name "/PSO_CS") (class "Default")
      (node (ref "M2") (pin "5") (pinfunction "~{CS}_5") (pintype "input"))
      (node (ref "U1") (pin "68") (pinfunction "IO_68") (pintype "bidirectional"))
    )
    (net (code "128") (name "/PSO_IO1") (class "Default")
      (node (ref "M2") (pin "2") (pinfunction "IO1_2") (pintype "bidirectional"))
      (node (ref "U1") (pin "63") (pinfunction "IO_63") (pintype "bidirectional"))
    )
    (net (code "129") (name "/PSO_IO2") (class "Default")
      (node (ref "M2") (pin "3") (pinfunction "IO2_3") (pintype "bidirectional"))
      (node (ref "U1") (pin "66") (pinfunction "IO_66") (pintype "bidirectional"))
    )
    (net (code "130") (name "/PSO_IO3") (class "Default")
      (node (ref "M2") (pin "4") (pinfunction "IO3_4") (pintype "bidirectional"))
      (node (ref "U1") (pin "67") (pinfunction "IO_67") (pintype "bidirectional"))
    )
    (net (code "131") (name "/PSO_MISO") (class "Default")
      (node (ref "M2") (pin "8") (pinfunction "MISO_8") (pintype "output"))
      (node (ref "U1") (pin "70") (pinfunction "IO_70") (pintype "bidirectional"))
    )
    (net (code "132") (name "/PSO_MOSI") (class "Default")
      (node (ref "M2") (pin "7") (pinfunction "MOSI_7") (pintype "input"))
      (node (ref "U1") (pin "69") (pinfunction "IO_69") (pintype "bidirectional"))
    )
    (net (code "133") (name "/PSO_SCLK") (class "Default")
      (node (ref "M2") (pin "9") (pinfunction "SCLK_9") (pintype "input"))
      (node (ref "U1") (pin "71") (pinfunction "IO_71") (pintype "bidirectional"))
    )
    (net (code "134") (name "3V3") (class "Default")
      (node (ref "C10") (pin "2") (pinfunction "2_2") (pintype "passive"))
      (node (ref "C2") (pin "2") (pinfunction "2_2") (pintype "passive"))
      (node (ref "C3") (pin "2") (pinfunction "2_2") (pintype "passive"))
      (node (ref "C4") (pin "2") (pinfunction "2_2") (pintype "passive"))
      (node (ref "C5") (pin "2") (pinfunction "2_2") (pintype "passive"))
      (node (ref "C6") (pin "2") (pinfunction "2_2") (pintype "passive"))
      (node (ref "C7") (pin "2") (pinfunction "2_2") (pintype "passive"))
      (node (ref "C8") (pin "2") (pinfunction "2_2") (pintype "passive"))
      (node (ref "C9") (pin "2") (pinfunction "2_2") (pintype "passive"))
      (node (ref "JTAG") (pin "4") (pinfunction "VREF_4") (pintype "power_in"))
      (node (ref "R1") (pin "1") (pinfunction "1_1") (pintype "passive"))
      (node (ref "R2") (pin "2") (pinfunction "2_2") (pintype "passive"))
      (node (ref "U1") (pin "100") (pinfunction "VCCIO2_100") (pintype "power_in"))
      (node (ref "U1") (pin "116") (pinfunction "VCCIO2_116") (pintype "power_in"))
      (node (ref "U1") (pin "126") (pinfunction "VCCINT_126") (pintype "power_in"))
      (node (ref "U1") (pin "136") (pinfunction "VCCIO2_136") (pintype "power_in"))
      (node (ref "U1") (pin "19") (pinfunction "VCCINT_19") (pintype "power_in"))
      (node (ref "U1") (pin "25") (pinfunction "VCCIO1_25") (pintype "power_in"))
      (node (ref "U1") (pin "46") (pinfunction "VCCIO1_46") (pintype "power_in"))
      (node (ref "U1") (pin "56") (pinfunction "VCCINT_56") (pintype "power_in"))
      (node (ref "U1") (pin "64") (pinfunction "VCCIO1_64") (pintype "power_in"))
      (node (ref "U1") (pin "82") (pinfunction "VCCIO2_82") (pintype "power_in"))
      (node (ref "U1") (pin "9") (pinfunction "VCCIO1_9") (pintype "power_in"))
      (node (ref "U1") (pin "90") (pinfunction "VCCINT_90") (pintype "power_in"))
      (node (ref "U2") (pin "2") (pinfunction "VOUT_2") (pintype "power_in"))
      (node (ref "X1") (pin "1") (pinfunction "OE_1") (pintype "input"))
      (node (ref "X1") (pin "4") (pinfunction "VCC_4") (pintype "power_in"))
    )
    (net (code "135") (name "GND") (class "Default")
      (node (ref "C1") (pin "1") (pinfunction "1_1") (pintype "passive"))
      (node (ref "C10") (pin "1") (pinfunction "1_1") (pintype "passive"))
      (node (ref "C2") (pin "1") (pinfunction "1_1") (pintype "passive"))
      (node (ref "C3") (pin "1") (pinfunction "1_1") (pintype "passive"))
      (node (ref "C4") (pin "1") (pinfunction "1_1") (pintype "passive"))
      (node (ref "C5") (pin "1") (pinfunction "1_1") (pintype "passive"))
      (node (ref "C6") (pin "1") (pinfunction "1_1") (pintype "passive"))
      (node (ref "C7") (pin "1") (pinfunction "1_1") (pintype "passive"))
      (node (ref "C8") (pin "1") (pinfunction "1_1") (pintype "passive"))
      (node (ref "C9") (pin "1") (pinfunction "1_1") (pintype "passive"))
      (node (ref "JTAG") (pin "10") (pinfunction "GND_10") (pintype "power_in"))
      (node (ref "JTAG") (pin "2") (pinfunction "GND_2") (pintype "power_in"))
      (node (ref "LED1") (pin "2") (pinfunction "K_2") (pintype "passive"))
      (node (ref "M1") (pin "1") (pinfunction "GND_1") (pintype "power_in"))
      (node (ref "M1") (pin "2") (pinfunction "GND_2") (pintype "power_in"))
      (node (ref "M1") (pin "27") (pinfunction "GND_27") (pintype "power_in"))
      (node (ref "M1") (pin "28") (pinfunction "GND_28") (pintype "power_in"))
      (node (ref "M1") (pin "29") (pinfunction "GND_29") (pintype "power_in"))
      (node (ref "M1") (pin "3") (pinfunction "GND_3") (pintype "power_in"))
      (node (ref "M1") (pin "30") (pinfunction "GND_30") (pintype "power_in"))
      (node (ref "M1") (pin "4") (pinfunction "GND_4") (pintype "power_in"))
      (node (ref "M2") (pin "1") (pinfunction "GND_1") (pintype "power_in"))
      (node (ref "M2") (pin "10") (pinfunction "GND_10") (pintype "power_in"))
      (node (ref "M2") (pin "6") (pinfunction "GND_6") (pintype "power_in"))
      (node (ref "P2") (pin "1") (pinfunction "1_1") (pintype "passive"))
      (node (ref "P2") (pin "2") (pinfunction "2_2") (pintype "passive"))
      (node (ref "P2") (pin "27") (pinfunction "27_27") (pintype "passive"))
      (node (ref "P2") (pin "28") (pinfunction "28_28") (pintype "passive"))
      (node (ref "PWR2") (pin "2") (pinfunction "-_2") (pintype "passive"))
      (node (ref "R3") (pin "2") (pinfunction "2_2") (pintype "passive"))
      (node (ref "RP11") (pin "2") (pinfunction "2_2") (pintype "passive"))
      (node (ref "RP11") (pin "4") (pinfunction "4_4") (pintype "passive"))
      (node (ref "RP11") (pin "6") (pinfunction "6_6") (pintype "passive"))
      (node (ref "RP11") (pin "8") (pinfunction "8_8") (pintype "passive"))
      (node (ref "RP12") (pin "2") (pinfunction "2_2") (pintype "passive"))
      (node (ref "RP12") (pin "4") (pinfunction "4_4") (pintype "passive"))
      (node (ref "RP12") (pin "6") (pinfunction "6_6") (pintype "passive"))
      (node (ref "RP12") (pin "8") (pinfunction "8_8") (pintype "passive"))
      (node (ref "RP13") (pin "2") (pinfunction "2_2") (pintype "passive"))
      (node (ref "RP13") (pin "4") (pinfunction "4_4") (pintype "passive"))
      (node (ref "RP13") (pin "6") (pinfunction "6_6") (pintype "passive"))
      (node (ref "RP13") (pin "8") (pinfunction "8_8") (pintype "passive"))
      (node (ref "RP14") (pin "2") (pinfunction "2_2") (pintype "passive"))
      (node (ref "RP14") (pin "4") (pinfunction "4_4") (pintype "passive"))
      (node (ref "RP14") (pin "6") (pinfunction "6_6") (pintype "passive"))
      (node (ref "RP14") (pin "8") (pinfunction "8_8") (pintype "passive"))
      (node (ref "RP15") (pin "2") (pinfunction "2_2") (pintype "passive"))
      (node (ref "RP15") (pin "4") (pinfunction "4_4") (pintype "passive"))
      (node (ref "RP15") (pin "6") (pinfunction "6_6") (pintype "passive"))
      (node (ref "RP15") (pin "8") (pinfunction "8_8") (pintype "passive"))
      (node (ref "RP16") (pin "2") (pinfunction "2_2") (pintype "passive"))
      (node (ref "RP16") (pin "4") (pinfunction "4_4") (pintype "passive"))
      (node (ref "RP16") (pin "6") (pinfunction "6_6") (pintype "passive"))
      (node (ref "RP16") (pin "8") (pinfunction "8_8") (pintype "passive"))
      (node (ref "RP17") (pin "2") (pinfunction "2_2") (pintype "passive"))
      (node (ref "RP17") (pin "4") (pinfunction "4_4") (pintype "passive"))
      (node (ref "RP17") (pin "6") (pinfunction "6_6") (pintype "passive"))
      (node (ref "RP17") (pin "8") (pinfunction "8_8") (pintype "passive"))
      (node (ref "RP18") (pin "2") (pinfunction "2_2") (pintype "passive"))
      (node (ref "RP18") (pin "4") (pinfunction "4_4") (pintype "passive"))
      (node (ref "RP18") (pin "6") (pinfunction "6_6") (pintype "passive"))
      (node (ref "RP18") (pin "8") (pinfunction "8_8") (pintype "passive"))
      (node (ref "RP19") (pin "2") (pinfunction "2_2") (pintype "passive"))
      (node (ref "RP19") (pin "4") (pinfunction "4_4") (pintype "passive"))
      (node (ref "RP19") (pin "6") (pinfunction "6_6") (pintype "passive"))
      (node (ref "RP19") (pin "8") (pinfunction "8_8") (pintype "passive"))
      (node (ref "RP20") (pin "2") (pinfunction "2_2") (pintype "passive"))
      (node (ref "RP20") (pin "4") (pinfunction "4_4") (pintype "passive"))
      (node (ref "RP20") (pin "6") (pinfunction "6_6") (pintype "passive"))
      (node (ref "RP20") (pin "8") (pinfunction "8_8") (pintype "passive"))
      (node (ref "U1") (pin "10") (pinfunction "GNDIO_10") (pintype "power_in"))
      (node (ref "U1") (pin "115") (pinfunction "GNDIO_115") (pintype "power_in"))
      (node (ref "U1") (pin "128") (pinfunction "GNDINT_128") (pintype "power_in"))
      (node (ref "U1") (pin "135") (pinfunction "GNDIO_135") (pintype "power_in"))
      (node (ref "U1") (pin "17") (pinfunction "GNDINT_17") (pintype "power_in"))
      (node (ref "U1") (pin "26") (pinfunction "GNDIO_26") (pintype "power_in"))
      (node (ref "U1") (pin "47") (pinfunction "GNDIO_47") (pintype "power_in"))
      (node (ref "U1") (pin "54") (pinfunction "GNDINT_54") (pintype "power_in"))
      (node (ref "U1") (pin "65") (pinfunction "GNDIO_65") (pintype "power_in"))
      (node (ref "U1") (pin "83") (pinfunction "GNDIO_83") (pintype "power_in"))
      (node (ref "U1") (pin "92") (pinfunction "GNDINT_92") (pintype "power_in"))
      (node (ref "U1") (pin "99") (pinfunction "GNDIO_99") (pintype "power_in"))
      (node (ref "U2") (pin "1") (pinfunction "GROUND_1") (pintype "power_in"))
      (node (ref "USB1") (pin "1") (pinfunction "G_1") (pintype "passive"))
      (node (ref "USB1") (pin "6") (pinfunction "S_6") (pintype "passive"))
      (node (ref "X1") (pin "2") (pinfunction "GND_2") (pintype "power_in"))
    )
    (net (code "136") (name "Net-(JTAG-TCK)") (class "Default")
      (node (ref "JTAG") (pin "1") (pinfunction "TCK_1") (pintype "output"))
      (node (ref "R3") (pin "1") (pinfunction "1_1") (pintype "passive"))
      (node (ref "RP21") (pin "4") (pinfunction "4_4") (pintype "passive"))
    )
    (net (code "137") (name "Net-(JTAG-TDI)") (class "Default")
      (node (ref "JTAG") (pin "9") (pinfunction "TDI_9") (pintype "output"))
      (node (ref "RP21") (pin "6") (pinfunction "6_6") (pintype "passive"))
    )
    (net (code "138") (name "Net-(JTAG-TDO)") (class "Default")
      (node (ref "JTAG") (pin "3") (pinfunction "TDO_3") (pintype "input"))
      (node (ref "RP21") (pin "2") (pinfunction "2_2") (pintype "passive"))
    )
    (net (code "139") (name "Net-(JTAG-TMS)") (class "Default")
      (node (ref "JTAG") (pin "5") (pinfunction "TMS_5") (pintype "output"))
      (node (ref "R2") (pin "1") (pinfunction "1_1") (pintype "passive"))
      (node (ref "RP21") (pin "8") (pinfunction "8_8") (pintype "passive"))
    )
    (net (code "140") (name "Net-(LED1-A)") (class "Default")
      (node (ref "LED1") (pin "1") (pinfunction "A_1") (pintype "passive"))
      (node (ref "R1") (pin "2") (pinfunction "2_2") (pintype "passive"))
    )
    (net (code "141") (name "Net-(PWR2-+)") (class "Default")
      (node (ref "C1") (pin "2") (pinfunction "2_2") (pintype "passive"))
      (node (ref "PWR2") (pin "1") (pinfunction "+_1") (pintype "passive"))
      (node (ref "U2") (pin "3") (pinfunction "VIN_3") (pintype "power_in"))
      (node (ref "USB1") (pin "5") (pinfunction "V+_5") (pintype "passive"))
    )
    (net (code "142") (name "Net-(R4-Pad1)") (class "Default")
      (node (ref "R4") (pin "1") (pinfunction "1_1") (pintype "passive"))
      (node (ref "U1") (pin "72") (pinfunction "IO_72") (pintype "bidirectional"))
    )
    (net (code "143") (name "Net-(U1C-TCK)") (class "Default")
      (node (ref "RP21") (pin "3") (pinfunction "3_3") (pintype "passive"))
      (node (ref "U1") (pin "35") (pinfunction "TCK_35") (pintype "input"))
    )
    (net (code "144") (name "Net-(U1C-TDI)") (class "Default")
      (node (ref "RP21") (pin "5") (pinfunction "5_5") (pintype "passive"))
      (node (ref "U1") (pin "34") (pinfunction "TDI_34") (pintype "input"))
    )
    (net (code "145") (name "Net-(U1C-TDO)") (class "Default")
      (node (ref "RP21") (pin "1") (pinfunction "1_1") (pintype "passive"))
      (node (ref "U1") (pin "36") (pinfunction "TDO_36") (pintype "output"))
    )
    (net (code "146") (name "Net-(U1C-TMS)") (class "Default")
      (node (ref "RP21") (pin "7") (pinfunction "7_7") (pintype "passive"))
      (node (ref "U1") (pin "33") (pinfunction "TMS_33") (pintype "input"))
    )
    (net (code "147") (name "Net-(X1-OSCOUT)") (class "Default")
      (node (ref "R4") (pin "2") (pinfunction "2_2") (pintype "passive"))
      (node (ref "X1") (pin "3") (pinfunction "OSCOUT_3") (pintype "output"))
    )
    (net (code "148") (name "unconnected-(U1A-IO-Pad37)") (class "Default")
      (node (ref "U1") (pin "37") (pinfunction "IO_37") (pintype "bidirectional"))
    )
    (net (code "149") (name "unconnected-(U1A-IO-Pad38)") (class "Default")
      (node (ref "U1") (pin "38") (pinfunction "IO_38") (pintype "bidirectional"))
    )
    (net (code "150") (name "unconnected-(U1A-IO-Pad39)") (class "Default")
      (node (ref "U1") (pin "39") (pinfunction "IO_39") (pintype "bidirectional"))
    )
    (net (code "151") (name "unconnected-(U1A-IO-Pad40)") (class "Default")
      (node (ref "U1") (pin "40") (pinfunction "IO_40") (pintype "bidirectional"))
    )
    (net (code "152") (name "unconnected-(U1A-IO-Pad41)") (class "Default")
      (node (ref "U1") (pin "41") (pinfunction "IO_41") (pintype "bidirectional"))
    )
    (net (code "153") (name "unconnected-(U1A-IO-Pad42)") (class "Default")
      (node (ref "U1") (pin "42") (pinfunction "IO_42") (pintype "bidirectional"))
    )
    (net (code "154") (name "unconnected-(U1A-IO-Pad43)") (class "Default")
      (node (ref "U1") (pin "43") (pinfunction "IO_43") (pintype "bidirectional"))
    )
    (net (code "155") (name "unconnected-(U1A-IO-Pad44)") (class "Default")
      (node (ref "U1") (pin "44") (pinfunction "IO_44") (pintype "bidirectional"))
    )
    (net (code "156") (name "unconnected-(U1A-IO-Pad45)") (class "Default")
      (node (ref "U1") (pin "45") (pinfunction "IO_45") (pintype "bidirectional"))
    )
    (net (code "157") (name "unconnected-(U1A-IO-Pad48)") (class "Default")
      (node (ref "U1") (pin "48") (pinfunction "IO_48") (pintype "bidirectional"))
    )
    (net (code "158") (name "unconnected-(U1A-IO-Pad49)") (class "Default")
      (node (ref "U1") (pin "49") (pinfunction "IO_49") (pintype "bidirectional"))
    )
    (net (code "159") (name "unconnected-(U1A-IO-Pad50)") (class "Default")
      (node (ref "U1") (pin "50") (pinfunction "IO_50") (pintype "bidirectional"))
    )
    (net (code "160") (name "unconnected-(U1A-IO-Pad51)") (class "Default")
      (node (ref "U1") (pin "51") (pinfunction "IO_51") (pintype "bidirectional"))
    )
    (net (code "161") (name "unconnected-(U1A-IO-Pad52)") (class "Default")
      (node (ref "U1") (pin "52") (pinfunction "IO_52") (pintype "bidirectional"))
    )
    (net (code "162") (name "unconnected-(U1A-IO-Pad53)") (class "Default")
      (node (ref "U1") (pin "53") (pinfunction "IO_53") (pintype "bidirectional"))
    )
    (net (code "163") (name "unconnected-(U1A-IO-Pad55)") (class "Default")
      (node (ref "U1") (pin "55") (pinfunction "IO_55") (pintype "bidirectional"))
    )
    (net (code "164") (name "unconnected-(U1A-IO-Pad57)") (class "Default")
      (node (ref "U1") (pin "57") (pinfunction "IO_57") (pintype "bidirectional"))
    )
    (net (code "165") (name "unconnected-(U1A-IO-Pad58)") (class "Default")
      (node (ref "U1") (pin "58") (pinfunction "IO_58") (pintype "bidirectional"))
    )
    (net (code "166") (name "unconnected-(U1A-IO-Pad59)") (class "Default")
      (node (ref "U1") (pin "59") (pinfunction "IO_59") (pintype "bidirectional"))
    )
    (net (code "167") (name "unconnected-(U1A-IO-Pad62)") (class "Default")
      (node (ref "U1") (pin "62") (pinfunction "IO_62") (pintype "bidirectional"))
    )
    (net (code "168") (name "unconnected-(U1A-IO{slash}DEV_CLRn-Pad61)") (class "Default")
      (node (ref "U1") (pin "61") (pinfunction "IO/DEV_CLRn_61") (pintype "bidirectional"))
    )
    (net (code "169") (name "unconnected-(U1A-IO{slash}DEV_OE-Pad60)") (class "Default")
      (node (ref "U1") (pin "60") (pinfunction "IO/DEV_OE_60") (pintype "bidirectional"))
    )
    (net (code "170") (name "unconnected-(USB1-DM-Pad4)") (class "Default")
      (node (ref "USB1") (pin "4") (pinfunction "DM_4") (pintype "passive"))
    )
    (net (code "171") (name "unconnected-(USB1-DP-Pad3)") (class "Default")
      (node (ref "USB1") (pin "3") (pinfunction "DP_3") (pintype "passive"))
    )
    (net (code "172") (name "unconnected-(USB1-ID-Pad2)") (class "Default")
      (node (ref "USB1") (pin "2") (pinfunction "ID_2") (pintype "passive"))
    )
  )
)
